# 12V24V_led_driver-1.net
KiCad netlist of a schematic drawn in EAGLE
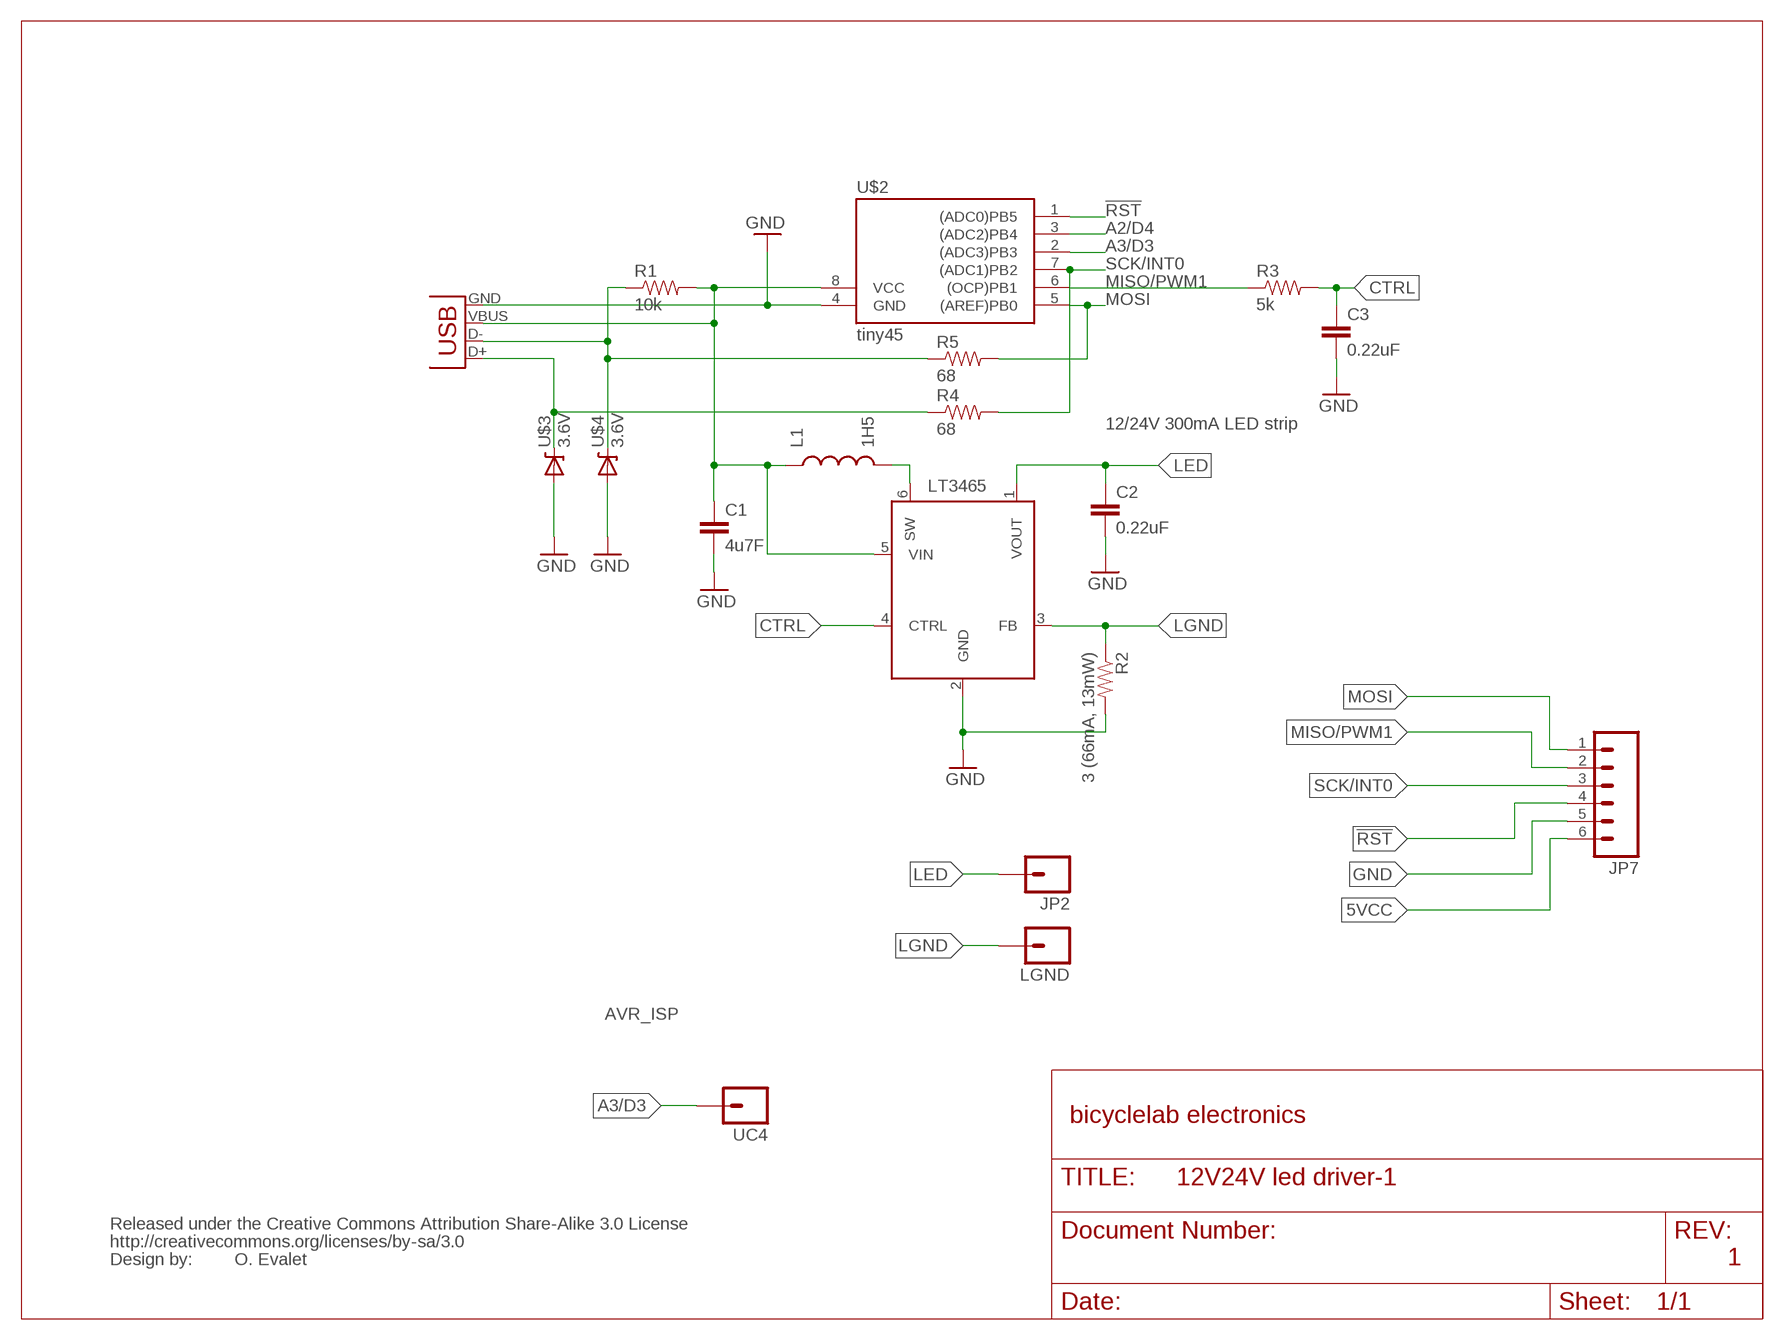
[diagram p0: schematic, sheet 1]

(export (version "E")
  (design (tool "Eeschema 10.0.6"))
  (components
    (comp (ref "C1")
      (value "4u7F")
      (footprint "eagle-import:0805")
      (libsource (lib "eagle-import") (part "CAP0805"))
    )
    (comp (ref "C2")
      (value "0.22uF")
      (footprint "eagle-import:0603-CAP")
      (libsource (lib "eagle-import") (part "CAP0603-CAP"))
    )
    (comp (ref "C3")
      (value "0.22uF")
      (footprint "eagle-import:0805")
      (libsource (lib "eagle-import") (part "CAP0805"))
    )
    (comp (ref "JP2")
      (value "M01PTH")
      (footprint "eagle-import:1X01")
      (libsource (lib "eagle-import") (part "M01PTH"))
    )
    (comp (ref "JP7")
      (value "M06EM406")
      (footprint "eagle-import:EM406")
      (libsource (lib "eagle-import") (part "M06EM406"))
    )
    (comp (ref "L1")
      (value "1H5")
      (footprint "eagle-import:0805")
      (libsource (lib "eagle-import") (part "INDUCTOR0805"))
    )
    (comp (ref "LGND")
      (value "M01PTH")
      (footprint "eagle-import:1X01")
      (libsource (lib "eagle-import") (part "M01PTH"))
    )
    (comp (ref "MISB-SW-5B")
      (value "MISB-SW-5B")
      (footprint "eagle-import:USB-MICROB")
      (libsource (lib "eagle-import") (part "USB-MICROB"))
    )
    (comp (ref "R1")
      (value "10k")
      (footprint "eagle-import:0805")
      (libsource (lib "eagle-import") (part "RESISTOR"))
    )
    (comp (ref "R2")
      (value "3 (66mA, 13mW)")
      (footprint "eagle-import:1206")
      (libsource (lib "eagle-import") (part "RESISTOR1206"))
    )
    (comp (ref "R3")
      (value "5k")
      (footprint "eagle-import:0805")
      (libsource (lib "eagle-import") (part "RESISTOR"))
    )
    (comp (ref "R4")
      (value "68")
      (footprint "eagle-import:0805")
      (libsource (lib "eagle-import") (part "RESISTOR"))
    )
    (comp (ref "R5")
      (value "68")
      (footprint "eagle-import:0805")
      (libsource (lib "eagle-import") (part "RESISTOR"))
    )
    (comp (ref "U$1")
      (value "LT365")
      (footprint "eagle-import:TSOT23-6_DDC")
      (libsource (lib "eagle-import") (part "LT365"))
    )
    (comp (ref "U$2")
      (value "tiny45")
      (footprint "eagle-import:SOIC8")
      (libsource (lib "eagle-import") (part "TINY25/45/85-20SU"))
    )
    (comp (ref "U$3")
      (value "3.6V")
      (footprint "eagle-import:SOD-323")
      (libsource (lib "eagle-import") (part "DIODE-ZENER-BZT52"))
    )
    (comp (ref "U$4")
      (value "3.6V")
      (footprint "eagle-import:SOD-323")
      (libsource (lib "eagle-import") (part "DIODE-ZENER-BZT52"))
    )
    (comp (ref "U$5")
      (value "CREATIVE_COMMONS")
      (footprint "eagle-import:CREATIVE_COMMONS")
      (libsource (lib "eagle-import") (part "CREATIVE_COMMONS"))
    )
    (comp (ref "UC4")
      (value "M01SMD-4.5X1.5")
      (footprint "eagle-import:PAD-1.5X4.5")
      (libsource (lib "eagle-import") (part "M01SMD-4.5X1.5"))
    )
  )
  (nets
    (net (code "1") (name "/A2{slash}D4") (class "Default")
      (node (ref "U$2") (pin "3") (pinfunction "(ADC2)PB4_3") (pintype "bidirectional"))
    )
    (net (code "2") (name "/~{RST}") (class "Default")
      (node (ref "JP7") (pin "4") (pinfunction "4_4") (pintype "passive"))
      (node (ref "U$2") (pin "1") (pinfunction "(ADC0)PB5_1") (pintype "bidirectional"))
    )
    (net (code "3") (name "5VCC") (class "Default")
      (node (ref "C1") (pin "1") (pinfunction "1_1") (pintype "passive"))
      (node (ref "JP7") (pin "6") (pinfunction "6_6") (pintype "passive"))
      (node (ref "L1") (pin "1") (pinfunction "1_1") (pintype "passive"))
      (node (ref "MISB-SW-5B") (pin "VBUS") (pinfunction "VBUS_VBUS") (pintype "bidirectional"))
      (node (ref "R1") (pin "2") (pinfunction "2_2") (pintype "passive"))
      (node (ref "U$1") (pin "5") (pinfunction "VIN_5") (pintype "input"))
      (node (ref "U$2") (pin "8") (pinfunction "VCC_8") (pintype "power_in"))
    )
    (net (code "4") (name "A3{slash}D3") (class "Default")
      (node (ref "U$2") (pin "2") (pinfunction "(ADC3)PB3_2") (pintype "bidirectional"))
      (node (ref "UC4") (pin "P$1") (pinfunction "1_P$1") (pintype "passive"))
    )
    (net (code "5") (name "CTRL") (class "Default")
      (node (ref "C3") (pin "1") (pinfunction "1_1") (pintype "passive"))
      (node (ref "R3") (pin "2") (pinfunction "2_2") (pintype "passive"))
      (node (ref "U$1") (pin "4") (pinfunction "CTRL_4") (pintype "input"))
    )
    (net (code "6") (name "GND") (class "Default")
      (node (ref "C1") (pin "2") (pinfunction "2_2") (pintype "passive"))
      (node (ref "C2") (pin "2") (pinfunction "2_2") (pintype "passive"))
      (node (ref "C3") (pin "2") (pinfunction "2_2") (pintype "passive"))
      (node (ref "JP7") (pin "5") (pinfunction "5_5") (pintype "passive"))
      (node (ref "MISB-SW-5B") (pin "GND") (pinfunction "GND_GND") (pintype "bidirectional"))
      (node (ref "R2") (pin "2") (pinfunction "2_2") (pintype "passive"))
      (node (ref "U$1") (pin "2") (pinfunction "GND_2") (pintype "power_in"))
      (node (ref "U$2") (pin "4") (pinfunction "GND_4") (pintype "power_in"))
      (node (ref "U$3") (pin "2") (pinfunction "A_2") (pintype "passive"))
      (node (ref "U$4") (pin "2") (pinfunction "A_2") (pintype "passive"))
    )
    (net (code "7") (name "LED") (class "Default")
      (node (ref "C2") (pin "1") (pinfunction "1_1") (pintype "passive"))
      (node (ref "JP2") (pin "1") (pinfunction "1_1") (pintype "passive"))
      (node (ref "U$1") (pin "1") (pinfunction "VOUT_1") (pintype "passive"))
    )
    (net (code "8") (name "LGND") (class "Default")
      (node (ref "LGND") (pin "1") (pinfunction "1_1") (pintype "passive"))
      (node (ref "R2") (pin "1") (pinfunction "1_1") (pintype "passive"))
      (node (ref "U$1") (pin "3") (pinfunction "FB_3") (pintype "passive"))
    )
    (net (code "9") (name "MISO{slash}PWM1") (class "Default")
      (node (ref "JP7") (pin "2") (pinfunction "2_2") (pintype "passive"))
      (node (ref "R3") (pin "1") (pinfunction "1_1") (pintype "passive"))
      (node (ref "U$2") (pin "6") (pinfunction "(OCP)PB1_6") (pintype "bidirectional"))
    )
    (net (code "10") (name "MOSI") (class "Default")
      (node (ref "JP7") (pin "1") (pinfunction "1_1") (pintype "passive"))
      (node (ref "R5") (pin "2") (pinfunction "2_2") (pintype "passive"))
      (node (ref "U$2") (pin "5") (pinfunction "(AREF)PB0_5") (pintype "bidirectional"))
    )
    (net (code "11") (name "Net-(U$1-SW)") (class "Default")
      (node (ref "L1") (pin "2") (pinfunction "2_2") (pintype "passive"))
      (node (ref "U$1") (pin "6") (pinfunction "SW_6") (pintype "passive"))
    )
    (net (code "12") (name "Net-(U$3-C)") (class "Default")
      (node (ref "MISB-SW-5B") (pin "D+") (pinfunction "D+_D+") (pintype "bidirectional"))
      (node (ref "R4") (pin "1") (pinfunction "1_1") (pintype "passive"))
      (node (ref "U$3") (pin "1") (pinfunction "C_1") (pintype "passive"))
    )
    (net (code "13") (name "Net-(U$4-C)") (class "Default")
      (node (ref "MISB-SW-5B") (pin "D-") (pinfunction "D-_D-") (pintype "bidirectional"))
      (node (ref "R1") (pin "1") (pinfunction "1_1") (pintype "passive"))
      (node (ref "R5") (pin "1") (pinfunction "1_1") (pintype "passive"))
      (node (ref "U$4") (pin "1") (pinfunction "C_1") (pintype "passive"))
    )
    (net (code "14") (name "SCK{slash}INT0") (class "Default")
      (node (ref "JP7") (pin "3") (pinfunction "3_3") (pintype "passive"))
      (node (ref "R4") (pin "2") (pinfunction "2_2") (pintype "passive"))
      (node (ref "U$2") (pin "7") (pinfunction "(ADC1)PB2_7") (pintype "bidirectional"))
    )
  )
)
